# F405_V3_0_Red.net
KiCad netlist of a schematic drawn in Altium Designer
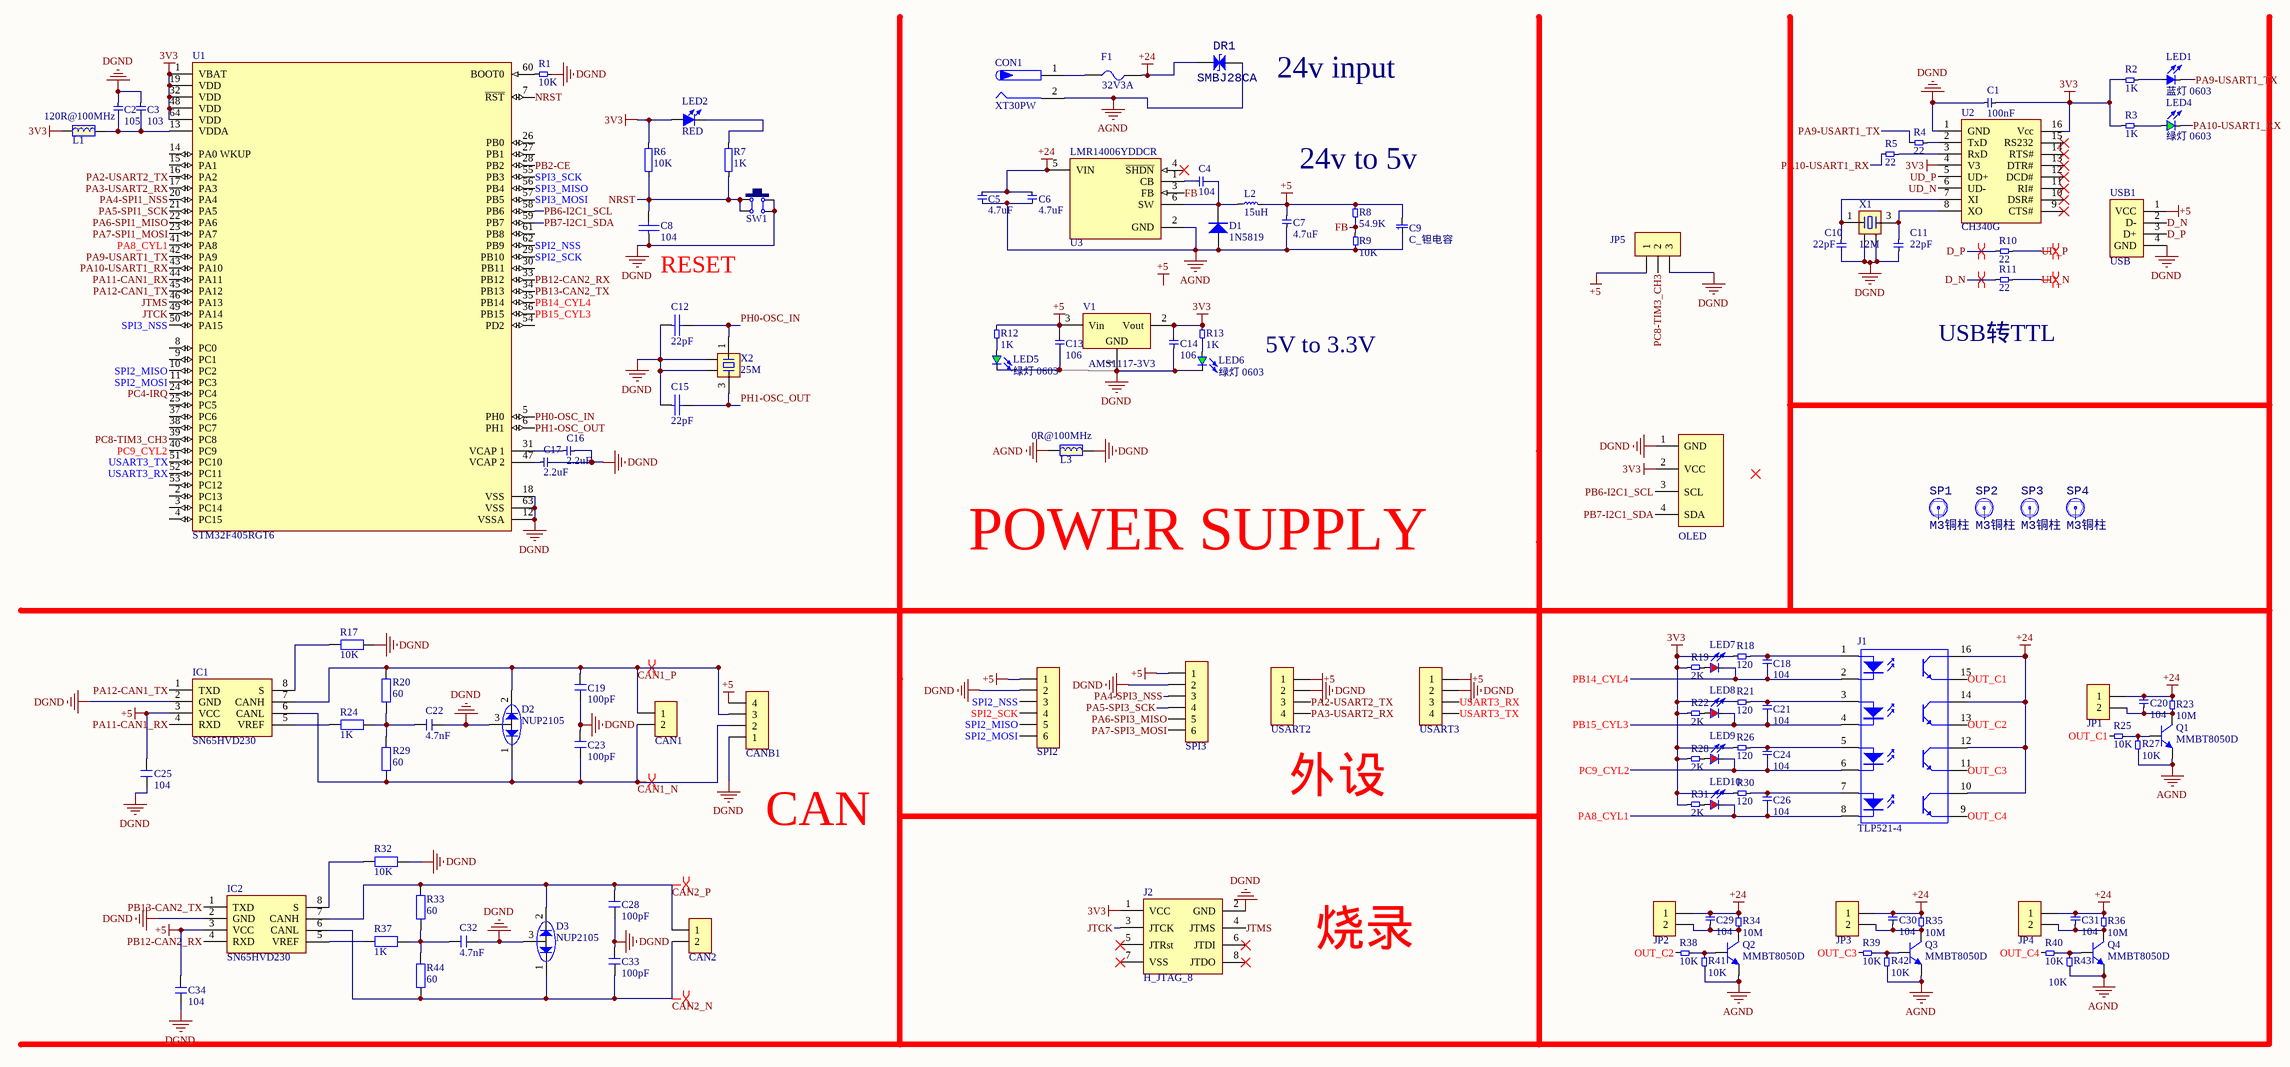
[diagram p0: F405_V3.0_Red.SchDoc]

(export (version "E")
  (design (tool "Eeschema 10.0.6"))
  (components
    (comp (ref "C1")
      (value "100nF")
      (footprint "C_0603")
      (description "无极性贴片电容")
      (libsource (lib "电阻电容电感库") (part "C_无极贴片"))
    )
    (comp (ref "C2")
      (value "105")
      (footprint "C_0603")
      (description "无极性贴片电容")
      (libsource (lib "电阻电容电感库") (part "C_无极贴片"))
    )
    (comp (ref "C3")
      (value "103")
      (footprint "C_0603")
      (description "无极性贴片电容")
      (libsource (lib "电阻电容电感库") (part "C_无极贴片"))
    )
    (comp (ref "C4")
      (value "104")
      (footprint "C_0603")
      (description "无极性贴片电容")
      (libsource (lib "电阻电容电感库") (part "C_无极贴片"))
    )
    (comp (ref "C5")
      (value "4.7uF")
      (footprint "C_0603")
      (description "无极性贴片电容")
      (libsource (lib "电阻电容电感库") (part "C_无极贴片"))
    )
    (comp (ref "C6")
      (value "4.7uF")
      (footprint "C_0603")
      (description "无极性贴片电容")
      (libsource (lib "电阻电容电感库") (part "C_无极贴片"))
    )
    (comp (ref "C7")
      (value "4.7uF")
      (footprint "C_0603")
      (description "无极性贴片电容")
      (libsource (lib "电阻电容电感库") (part "C_无极贴片"))
    )
    (comp (ref "C8")
      (value "104")
      (footprint "C 0603_L")
      (description "Capacitor")
      (libsource (lib "F446") (part "普通电容"))
    )
    (comp (ref "C9")
      (value "C_钽电容")
      (footprint "C_T-B_1210/3528-21")
      (description "有极性贴片钽电容")
      (libsource (lib "电阻电容电感库") (part "C_钽电容"))
    )
    (comp (ref "C10")
      (value "22pF")
      (footprint "C_0603")
      (description "无极性贴片电容")
      (libsource (lib "电阻电容电感库") (part "C_无极贴片"))
    )
    (comp (ref "C11")
      (value "22pF")
      (footprint "C_0603")
      (description "无极性贴片电容")
      (libsource (lib "电阻电容电感库") (part "C_无极贴片"))
    )
    (comp (ref "C12")
      (value "22pF")
      (footprint "C 0603_L")
      (description "Capacitor")
      (libsource (lib "F446") (part "普通电容"))
    )
    (comp (ref "C13")
      (value "106")
      (footprint "C_0603")
      (description "无极性贴片电容")
      (libsource (lib "电阻电容电感库") (part "C_无极贴片"))
    )
    (comp (ref "C14")
      (value "106")
      (footprint "C_0603")
      (description "无极性贴片电容")
      (libsource (lib "电阻电容电感库") (part "C_无极贴片"))
    )
    (comp (ref "C15")
      (value "22pF")
      (footprint "C 0603_L")
      (description "Capacitor")
      (libsource (lib "F446") (part "普通电容"))
    )
    (comp (ref "C16")
      (value "2.2uF")
      (footprint "C_0603")
      (description "无极性贴片电容")
      (libsource (lib "电阻电容电感库") (part "C_无极贴片"))
    )
    (comp (ref "C17")
      (value "2.2uF")
      (footprint "C_0603")
      (description "无极性贴片电容")
      (libsource (lib "电阻电容电感库") (part "C_无极贴片"))
    )
    (comp (ref "C18")
      (value "104")
      (footprint "C_0603")
      (description "无极性贴片电容")
      (libsource (lib "电阻电容电感库") (part "C_无极贴片"))
    )
    (comp (ref "C19")
      (value "100pF")
      (footprint "C 0603_L")
      (description "无极性贴片电容")
      (libsource (lib "3.1   - 电阻-电容-电感") (part "C"))
    )
    (comp (ref "C20")
      (value "104")
      (footprint "C_0603")
      (description "无极性贴片电容")
      (libsource (lib "电阻电容电感库") (part "C_无极贴片"))
    )
    (comp (ref "C21")
      (value "104")
      (footprint "C_0603")
      (description "无极性贴片电容")
      (libsource (lib "电阻电容电感库") (part "C_无极贴片"))
    )
    (comp (ref "C22")
      (value "4.7nF")
      (footprint "C 0603_L")
      (description "无极性贴片电容")
      (libsource (lib "3.1   - 电阻-电容-电感") (part "C"))
    )
    (comp (ref "C23")
      (value "100pF")
      (footprint "C 0603_L")
      (description "无极性贴片电容")
      (libsource (lib "3.1   - 电阻-电容-电感") (part "C"))
    )
    (comp (ref "C24")
      (value "104")
      (footprint "C_0603")
      (description "无极性贴片电容")
      (libsource (lib "电阻电容电感库") (part "C_无极贴片"))
    )
    (comp (ref "C25")
      (value "104")
      (footprint "C 0603_L")
      (description "无极性贴片电容")
      (libsource (lib "3.1   - 电阻-电容-电感") (part "C"))
    )
    (comp (ref "C26")
      (value "104")
      (footprint "C_0603")
      (description "无极性贴片电容")
      (libsource (lib "电阻电容电感库") (part "C_无极贴片"))
    )
    (comp (ref "C28")
      (value "100pF")
      (footprint "C 0603_L")
      (description "无极性贴片电容")
      (libsource (lib "3.1   - 电阻-电容-电感") (part "C"))
    )
    (comp (ref "C29")
      (value "104")
      (footprint "C_0603")
      (description "无极性贴片电容")
      (libsource (lib "电阻电容电感库") (part "C_无极贴片"))
    )
    (comp (ref "C30")
      (value "104")
      (footprint "C_0603")
      (description "无极性贴片电容")
      (libsource (lib "电阻电容电感库") (part "C_无极贴片"))
    )
    (comp (ref "C31")
      (value "104")
      (footprint "C_0603")
      (description "无极性贴片电容")
      (libsource (lib "电阻电容电感库") (part "C_无极贴片"))
    )
    (comp (ref "C32")
      (value "4.7nF")
      (footprint "C 0603_L")
      (description "无极性贴片电容")
      (libsource (lib "3.1   - 电阻-电容-电感") (part "C"))
    )
    (comp (ref "C33")
      (value "100pF")
      (footprint "C 0603_L")
      (description "无极性贴片电容")
      (libsource (lib "3.1   - 电阻-电容-电感") (part "C"))
    )
    (comp (ref "C34")
      (value "104")
      (footprint "C 0603_L")
      (description "无极性贴片电容")
      (libsource (lib "3.1   - 电阻-电容-电感") (part "C"))
    )
    (comp (ref "CAN1")
      (value "HDR-1X2")
      (footprint "XH2.54-LS-2P")
      (description "2P接插件")
      (libsource (lib "") (part "Header 2_1"))
    )
    (comp (ref "CAN2")
      (value "HDR-1X2")
      (footprint "XH2.54-LS-2P")
      (description "2P接插件")
      (libsource (lib "") (part "Header 2_1"))
    )
    (comp (ref "CANB1")
      (value "HDR-1X4")
      (footprint "XH2.54-LS-4P")
      (description "4P接插件")
      (libsource (lib "") (part "Header 4_1"))
    )
    (comp (ref "CON1")
      (value "XT30PW")
      (footprint "XT30PW-M")
      (description "XT30PW-M PCB板专用卧式连接器，低温升阻燃插头")
      (libsource (lib "AMASS") (part "XT30PW-M"))
    )
    (comp (ref "D1")
      (value "1N5819")
      (footprint "SOD-123")
      (description "肖特基二极管")
      (libsource (lib "8.1   - 二极管-整流桥") (part "1N5819"))
    )
    (comp (ref "D2")
      (value "NUP2105")
      (footprint "SOT23-3N")
      (description "表贴肖特基二极管")
      (libsource (lib "8.1   - 二极管-整流桥") (part "BAT54A"))
    )
    (comp (ref "D3")
      (value "NUP2105")
      (footprint "SOT23-3N")
      (description "表贴肖特基二极管")
      (libsource (lib "8.1   - 二极管-整流桥") (part "BAT54A"))
    )
    (comp (ref "DR1")
      (value "SMBJ28CA")
      (footprint "二极管-整流桥:SMB")
      (description "瞬态电压抑制二极管")
      (libsource (lib "8.1   - 二极管-整流桥") (part "DR"))
    )
    (comp (ref "F1")
      (value "32V3A")
      (footprint "FU 1206")
      (description "贴片保险丝")
      (libsource (lib "10.1 - 保险丝-晶振") (part "FU"))
    )
    (comp (ref "IC1")
      (value "SN65HVD230")
      (footprint "SOP8_M")
      (description "CAN芯片")
      (libsource (lib "F405底板") (part "SN65HVD1050"))
    )
    (comp (ref "IC2")
      (value "SN65HVD230")
      (footprint "SOP8_M")
      (description "CAN芯片")
      (libsource (lib "F405底板") (part "SN65HVD1050"))
    )
    (comp (ref "J1")
      (value "TLP521-4")
      (footprint "SOP16N_N")
      (description "4路开关光耦")
      (libsource (lib "11.1 - 传感元件") (part "TLP521-4"))
    )
    (comp (ref "J2")
      (value "H_JTAG_8")
      (footprint "IDC2.54-LI-2x4P")
      (description "调试器")
      (libsource (lib "F405") (part "H_JTAG_8"))
    )
    (comp (ref "JP1")
      (value "HDR-1X2")
      (footprint "XH2.54-LS-2P")
      (description "2P接插件")
      (libsource (lib "4.6   - 接插件-脚距2.54") (part "Header 2"))
    )
    (comp (ref "JP2")
      (value "HDR-1X2")
      (footprint "XH2.54-LS-2P")
      (description "2P接插件")
      (libsource (lib "4.6   - 接插件-脚距2.54") (part "Header 2"))
    )
    (comp (ref "JP3")
      (value "HDR-1X2")
      (footprint "XH2.54-LS-2P")
      (description "2P接插件")
      (libsource (lib "4.6   - 接插件-脚距2.54") (part "Header 2"))
    )
    (comp (ref "JP4")
      (value "HDR-1X2")
      (footprint "XH2.54-LS-2P")
      (description "2P接插件")
      (libsource (lib "4.6   - 接插件-脚距2.54") (part "Header 2"))
    )
    (comp (ref "JP5")
      (value "HDR-1X3")
      (footprint "XH2.54-LS-3P")
      (description "3P接插件")
      (libsource (lib "4.6   - 接插件-脚距2.54") (part "Header 3"))
    )
    (comp (ref "L1")
      (value "120R@100MHz")
      (footprint "L 0603_L")
      (description "磁珠")
      (libsource (lib "电阻电容电感库") (part "L_磁珠"))
    )
    (comp (ref "L2")
      (value "15uH")
      (footprint "CD43")
      (description "贴片屏蔽式功率电感")
      (libsource (lib "电阻电容电感库") (part "L_贴片功率"))
    )
    (comp (ref "L3")
      (value "0R@100MHz")
      (footprint "L 0603_L")
      (description "磁珠")
      (libsource (lib "电阻电容电感库") (part "L_磁珠"))
    )
    (comp (ref "LED1")
      (value "蓝灯 0603")
      (footprint "LED_SE")
      (description "发光二极管")
      (libsource (lib "LED") (part "0603 蓝灯"))
    )
    (comp (ref "LED2")
      (value "RED")
      (footprint "LED 0805R")
      (description "大功率LED")
      (libsource (lib "F446") (part "LED-SMD_1W"))
    )
    (comp (ref "LED4")
      (value "绿灯 0603")
      (footprint "LED_SE")
      (description "发光二极管")
      (libsource (lib "LED") (part "0603 绿灯"))
    )
    (comp (ref "LED5")
      (value "绿灯 0603")
      (footprint "LED_SE")
      (description "发光二极管")
      (libsource (lib "LED") (part "0603 绿灯"))
    )
    (comp (ref "LED6")
      (value "绿灯 0603")
      (footprint "LED_SE")
      (description "发光二极管")
      (libsource (lib "LED") (part "0603 绿灯"))
    )
    (comp (ref "LED7")
      (value "红灯 0603")
      (footprint "LED_SE")
      (description "发光二极管")
      (libsource (lib "LED") (part "0603 红灯"))
    )
    (comp (ref "LED8")
      (value "红灯 0603")
      (footprint "LED_SE")
      (description "发光二极管")
      (libsource (lib "LED") (part "0603 红灯"))
    )
    (comp (ref "LED9")
      (value "红灯 0603")
      (footprint "LED_SE")
      (description "发光二极管")
      (libsource (lib "LED") (part "0603 红灯"))
    )
    (comp (ref "LED10")
      (value "红灯 0603")
      (footprint "LED_SE")
      (description "发光二极管")
      (libsource (lib "LED") (part "0603 红灯"))
    )
    (comp (ref "OLED")
      (value "~")
      (footprint "OLED 4Pin 12864")
      (description "点阵屏")
      (libsource (lib "F446") (part "OLED"))
    )
    (comp (ref "Q1")
      (value "MMBT8050D")
      (footprint "SOT23-3N")
      (description "高压-NPN型")
      (libsource (lib "6.2   - 三极管") (part "MMBTA42"))
    )
    (comp (ref "Q2")
      (value "MMBT8050D")
      (footprint "SOT23-3N")
      (description "高压-NPN型")
      (libsource (lib "6.2   - 三极管") (part "MMBTA42"))
    )
    (comp (ref "Q3")
      (value "MMBT8050D")
      (footprint "SOT23-3N")
      (description "高压-NPN型")
      (libsource (lib "6.2   - 三极管") (part "MMBTA42"))
    )
    (comp (ref "Q4")
      (value "MMBT8050D")
      (footprint "SOT23-3N")
      (description "高压-NPN型")
      (libsource (lib "6.2   - 三极管") (part "MMBTA42"))
    )
    (comp (ref "R1")
      (value "10K")
      (footprint "R_0603")
      (description "贴片电阻")
      (libsource (lib "电阻电容电感库") (part "R_贴片"))
    )
    (comp (ref "R2")
      (value "1K")
      (footprint "R_0603")
      (description "贴片电阻")
      (libsource (lib "电阻电容电感库") (part "R_贴片"))
    )
    (comp (ref "R3")
      (value "1K")
      (footprint "R_0603")
      (description "贴片电阻")
      (libsource (lib "电阻电容电感库") (part "R_贴片"))
    )
    (comp (ref "R4")
      (value "22")
      (footprint "R_0603")
      (description "贴片电阻")
      (libsource (lib "电阻电容电感库") (part "R_贴片"))
    )
    (comp (ref "R5")
      (value "22")
      (footprint "R_0603")
      (description "贴片电阻")
      (libsource (lib "电阻电容电感库") (part "R_贴片"))
    )
    (comp (ref "R6") (value "10K") (footprint "R 0603_L") (libsource (lib "F446") (part "普通电阻")))
    (comp (ref "R7") (value "1K") (footprint "R 0603_L") (libsource (lib "F446") (part "普通电阻")))
    (comp (ref "R8")
      (value "54.9K")
      (footprint "R_0603")
      (description "贴片电阻")
      (libsource (lib "电阻电容电感库") (part "R_贴片"))
    )
    (comp (ref "R9")
      (value "10K")
      (footprint "R_0603")
      (description "贴片电阻")
      (libsource (lib "电阻电容电感库") (part "R_贴片"))
    )
    (comp (ref "R10")
      (value "22")
      (footprint "R_0603")
      (description "贴片电阻")
      (libsource (lib "电阻电容电感库") (part "R_贴片"))
    )
    (comp (ref "R11")
      (value "22")
      (footprint "R_0603")
      (description "贴片电阻")
      (libsource (lib "电阻电容电感库") (part "R_贴片"))
    )
    (comp (ref "R12")
      (value "1K")
      (footprint "R_0603")
      (description "贴片电阻")
      (libsource (lib "电阻电容电感库") (part "R_贴片"))
    )
    (comp (ref "R13")
      (value "1K")
      (footprint "R_0603")
      (description "贴片电阻")
      (libsource (lib "电阻电容电感库") (part "R_贴片"))
    )
    (comp (ref "R17")
      (value "10K")
      (footprint "R 0603_L")
      (description "贴片电阻")
      (libsource (lib "3.1   - 电阻-电容-电感") (part "R"))
    )
    (comp (ref "R18")
      (value "120")
      (footprint "R_0603")
      (description "贴片电阻")
      (libsource (lib "电阻电容电感库") (part "R_贴片"))
    )
    (comp (ref "R19")
      (value "2K")
      (footprint "R_0603")
      (description "贴片电阻")
      (libsource (lib "电阻电容电感库") (part "R_贴片"))
    )
    (comp (ref "R20")
      (value "60")
      (footprint "R 0603_L")
      (description "贴片电阻")
      (libsource (lib "3.1   - 电阻-电容-电感") (part "R"))
    )
    (comp (ref "R21")
      (value "120")
      (footprint "R_0603")
      (description "贴片电阻")
      (libsource (lib "电阻电容电感库") (part "R_贴片"))
    )
    (comp (ref "R22")
      (value "2K")
      (footprint "R_0603")
      (description "贴片电阻")
      (libsource (lib "电阻电容电感库") (part "R_贴片"))
    )
    (comp (ref "R23")
      (value "10M")
      (footprint "R_0805")
      (description "贴片电阻")
      (libsource (lib "电阻电容电感库") (part "R_贴片"))
    )
    (comp (ref "R24")
      (value "1K")
      (footprint "R 0603_L")
      (description "贴片电阻")
      (libsource (lib "3.1   - 电阻-电容-电感") (part "R"))
    )
    (comp (ref "R25")
      (value "10K")
      (footprint "R_0603")
      (description "贴片电阻")
      (libsource (lib "电阻电容电感库") (part "R_贴片"))
    )
    (comp (ref "R26")
      (value "120")
      (footprint "R_0603")
      (description "贴片电阻")
      (libsource (lib "电阻电容电感库") (part "R_贴片"))
    )
    (comp (ref "R27")
      (value "10K")
      (footprint "R_0603")
      (description "贴片电阻")
      (libsource (lib "电阻电容电感库") (part "R_贴片"))
    )
    (comp (ref "R28")
      (value "2K")
      (footprint "R_0603")
      (description "贴片电阻")
      (libsource (lib "电阻电容电感库") (part "R_贴片"))
    )
    (comp (ref "R29")
      (value "60")
      (footprint "R 0603_L")
      (description "贴片电阻")
      (libsource (lib "3.1   - 电阻-电容-电感") (part "R"))
    )
    (comp (ref "R30")
      (value "120")
      (footprint "R_0603")
      (description "贴片电阻")
      (libsource (lib "电阻电容电感库") (part "R_贴片"))
    )
    (comp (ref "R31")
      (value "2K")
      (footprint "R_0603")
      (description "贴片电阻")
      (libsource (lib "电阻电容电感库") (part "R_贴片"))
    )
    (comp (ref "R32")
      (value "10K")
      (footprint "R 0603_L")
      (description "贴片电阻")
      (libsource (lib "3.1   - 电阻-电容-电感") (part "R"))
    )
    (comp (ref "R33")
      (value "60")
      (footprint "R 0603_L")
      (description "贴片电阻")
      (libsource (lib "3.1   - 电阻-电容-电感") (part "R"))
    )
    (comp (ref "R34")
      (value "10M")
      (footprint "R_0805")
      (description "贴片电阻")
      (libsource (lib "电阻电容电感库") (part "R_贴片"))
    )
    (comp (ref "R35")
      (value "10M")
      (footprint "R_0805")
      (description "贴片电阻")
      (libsource (lib "电阻电容电感库") (part "R_贴片"))
    )
    (comp (ref "R36")
      (value "10M")
      (footprint "R_0805")
      (description "贴片电阻")
      (libsource (lib "电阻电容电感库") (part "R_贴片"))
    )
    (comp (ref "R37")
      (value "1K")
      (footprint "R 0603_L")
      (description "贴片电阻")
      (libsource (lib "3.1   - 电阻-电容-电感") (part "R"))
    )
    (comp (ref "R38")
      (value "10K")
      (footprint "R_0603")
      (description "贴片电阻")
      (libsource (lib "电阻电容电感库") (part "R_贴片"))
    )
    (comp (ref "R39")
      (value "10K")
      (footprint "R_0603")
      (description "贴片电阻")
      (libsource (lib "电阻电容电感库") (part "R_贴片"))
    )
    (comp (ref "R40")
      (value "10K")
      (footprint "R_0603")
      (description "贴片电阻")
      (libsource (lib "电阻电容电感库") (part "R_贴片"))
    )
    (comp (ref "R41")
      (value "10K")
      (footprint "R_0603")
      (description "贴片电阻")
      (libsource (lib "电阻电容电感库") (part "R_贴片"))
    )
    (comp (ref "R42")
      (value "10K")
      (footprint "R_0603")
      (description "贴片电阻")
      (libsource (lib "电阻电容电感库") (part "R_贴片"))
    )
    (comp (ref "R43")
      (value "10K")
      (footprint "R_0603")
      (description "贴片电阻")
      (libsource (lib "电阻电容电感库") (part "R_贴片"))
    )
    (comp (ref "R44")
      (value "60")
      (footprint "R 0603_L")
      (description "贴片电阻")
      (libsource (lib "3.1   - 电阻-电容-电感") (part "R"))
    )
    (comp (ref "SP1")
      (value "M3铜柱")
      (footprint "M3x4_L")
      (description "铜柱")
      (libsource (lib "15.1 - 未分类器件") (part "铜柱小焊盘"))
    )
    (comp (ref "SP2")
      (value "M3铜柱")
      (footprint "M3x4_L")
      (description "铜柱")
      (libsource (lib "15.1 - 未分类器件") (part "铜柱小焊盘"))
    )
    (comp (ref "SP3")
      (value "M3铜柱")
      (footprint "M3x4_L")
      (description "铜柱")
      (libsource (lib "15.1 - 未分类器件") (part "铜柱小焊盘"))
    )
    (comp (ref "SP4")
      (value "M3铜柱")
      (footprint "M3x4_L")
      (description "铜柱")
      (libsource (lib "15.1 - 未分类器件") (part "铜柱小焊盘"))
    )
    (comp (ref "SPI2")
      (value "HDR-1X6")
      (footprint "XH2.54-LS-6P")
      (description "6P接插件")
      (libsource (lib "钝角") (part "Header 6"))
    )
    (comp (ref "SPI3")
      (value "HDR-1X6")
      (footprint "XH2.54-LS-6P")
      (description "6P接插件")
      (libsource (lib "钝角") (part "Header 6"))
    )
    (comp (ref "SW1")
      (value "6x6x5")
      (footprint "TSW SMD-6*6*8")
      (description "贴片6x6轻触开关")
      (libsource (lib "5.1   - 按键-开关") (part "TSW SMD-6x6"))
    )
    (comp (ref "U1")
      (value "STM32F405RGT6")
      (footprint "LQFP64 10x10_N")
      (libsource (lib "2.1   - STM32系列单片机") (part "STM32F405RGT6"))
    )
    (comp (ref "U2")
      (value "CH340G")
      (footprint "SOP16_N")
      (description "串口转USB")
      (libsource (lib "1.1   - IC芯片") (part "CH340G"))
    )
    (comp (ref "U3")
      (value "LMR14006YDDCR")
      (footprint "SOT23-6L")
      (description "SIMPLE SWITCHER® 4-V to 40-V, 600-mA step-down converter with Low Iq 6-SOT-23-THIN -40 to 125")
      (libsource (lib "高级IC") (part "LMR14006YDDCR"))
    )
    (comp (ref "USART2")
      (value "HDR-1X4")
      (footprint "XH2.54-LS-4P")
      (description "4P接插件")
      (libsource (lib "4.6   - 接插件-脚距2.54") (part "Header 4"))
    )
    (comp (ref "USART3")
      (value "HDR-1X4")
      (footprint "XH2.54-LS-4P")
      (description "4P接插件")
      (libsource (lib "4.6   - 接插件-脚距2.54") (part "Header 4"))
    )
    (comp (ref "USB1")
      (value "USB")
      (footprint "USB-A/S_A")
      (description "USB-A型母接口")
      (libsource (lib "4.1   - 接口类") (part "USB-A/S"))
    )
    (comp (ref "V1")
      (value "AMS1117-3V3")
      (footprint "SOT223_N")
      (description "三端稳压芯片")
      (libsource (lib "1.3   - 电源类芯片") (part "AMS1117"))
    )
    (comp (ref "X1")
      (value "12M")
      (footprint "OSC 3225-4P")
      (description "4脚无源晶振")
      (libsource (lib "10.1 - 保险丝-晶振") (part "XTAL-4P"))
    )
    (comp (ref "X2")
      (value "25M")
      (footprint "OSC 3225-4P")
      (description "4脚无源晶振")
      (libsource (lib "F446") (part "XTAL-4P"))
    )
  )
  (nets
    (net (code "1") (name "+5") (class "Default")
      (node (ref "C13") (pin "2") (pinfunction "2_2") (pintype "passive"))
      (node (ref "C25") (pin "2") (pinfunction "2_2") (pintype "passive"))
      (node (ref "C34") (pin "2") (pinfunction "2_2") (pintype "passive"))
      (node (ref "C7") (pin "1") (pinfunction "1_1") (pintype "passive"))
      (node (ref "C9") (pin "2") (pinfunction "2_2") (pintype "passive"))
      (node (ref "CANB1") (pin "4") (pinfunction "4_4") (pintype "passive"))
      (node (ref "IC1") (pin "3") (pinfunction "VCC_3") (pintype "passive"))
      (node (ref "IC2") (pin "3") (pinfunction "VCC_3") (pintype "passive"))
      (node (ref "JP5") (pin "1") (pinfunction "1_1") (pintype "passive"))
      (node (ref "L2") (pin "2") (pinfunction "2_2") (pintype "passive"))
      (node (ref "R12") (pin "2") (pintype "passive"))
      (node (ref "R8") (pin "2") (pintype "passive"))
      (node (ref "SPI2") (pin "1") (pinfunction "1_1") (pintype "passive"))
      (node (ref "SPI3") (pin "1") (pinfunction "1_1") (pintype "passive"))
      (node (ref "USART2") (pin "1") (pinfunction "1_1") (pintype "passive"))
      (node (ref "USART3") (pin "1") (pinfunction "1_1") (pintype "passive"))
      (node (ref "USB1") (pin "1") (pinfunction "VCC_1") (pintype "passive"))
      (node (ref "V1") (pin "3") (pinfunction "Vin_3") (pintype "passive"))
    )
    (net (code "2") (name "+24") (class "Default")
      (node (ref "C20") (pin "2") (pinfunction "2_2") (pintype "passive"))
      (node (ref "C29") (pin "2") (pinfunction "2_2") (pintype "passive"))
      (node (ref "C30") (pin "2") (pinfunction "2_2") (pintype "passive"))
      (node (ref "C31") (pin "2") (pinfunction "2_2") (pintype "passive"))
      (node (ref "C5") (pin "2") (pinfunction "2_2") (pintype "passive"))
      (node (ref "C6") (pin "2") (pinfunction "2_2") (pintype "passive"))
      (node (ref "DR1") (pin "2") (pinfunction "K_2") (pintype "passive"))
      (node (ref "F1") (pin "2") (pinfunction "2_2") (pintype "passive"))
      (node (ref "J1") (pin "10") (pinfunction "4C_10") (pintype "passive"))
      (node (ref "J1") (pin "12") (pinfunction "3C_12") (pintype "passive"))
      (node (ref "J1") (pin "14") (pinfunction "2C_14") (pintype "passive"))
      (node (ref "J1") (pin "16") (pinfunction "1C_16") (pintype "passive"))
      (node (ref "JP1") (pin "1") (pinfunction "1_1") (pintype "passive"))
      (node (ref "JP2") (pin "1") (pinfunction "1_1") (pintype "passive"))
      (node (ref "JP3") (pin "1") (pinfunction "1_1") (pintype "passive"))
      (node (ref "JP4") (pin "1") (pinfunction "1_1") (pintype "passive"))
      (node (ref "R23") (pin "2") (pintype "passive"))
      (node (ref "R34") (pin "2") (pintype "passive"))
      (node (ref "R35") (pin "2") (pintype "passive"))
      (node (ref "R36") (pin "2") (pintype "passive"))
      (node (ref "U3") (pin "5") (pinfunction "VIN_5") (pintype "power_in"))
    )
    (net (code "3") (name "/CAN1_N") (class "Default")
      (node (ref "C23") (pin "2") (pinfunction "2_2") (pintype "passive"))
      (node (ref "CAN1") (pin "2") (pinfunction "2_2") (pintype "passive"))
      (node (ref "CANB1") (pin "2") (pinfunction "2_2") (pintype "passive"))
      (node (ref "D2") (pin "1") (pinfunction "1_1") (pintype "passive"))
      (node (ref "IC1") (pin "6") (pinfunction "CANL_6") (pintype "passive"))
      (node (ref "R29") (pin "2") (pinfunction "2_2") (pintype "passive"))
    )
    (net (code "4") (name "/CAN1_P") (class "Default")
      (node (ref "C19") (pin "1") (pinfunction "1_1") (pintype "passive"))
      (node (ref "CAN1") (pin "1") (pinfunction "1_1") (pintype "passive"))
      (node (ref "CANB1") (pin "3") (pinfunction "3_3") (pintype "passive"))
      (node (ref "D2") (pin "2") (pinfunction "2_2") (pintype "passive"))
      (node (ref "IC1") (pin "7") (pinfunction "CANH_7") (pintype "passive"))
      (node (ref "R20") (pin "2") (pinfunction "2_2") (pintype "passive"))
    )
    (net (code "5") (name "/CAN2_N") (class "Default")
      (node (ref "C33") (pin "2") (pinfunction "2_2") (pintype "passive"))
      (node (ref "CAN2") (pin "2") (pinfunction "2_2") (pintype "passive"))
      (node (ref "D3") (pin "1") (pinfunction "1_1") (pintype "passive"))
      (node (ref "IC2") (pin "6") (pinfunction "CANL_6") (pintype "passive"))
      (node (ref "R44") (pin "2") (pinfunction "2_2") (pintype "passive"))
    )
    (net (code "6") (name "/CAN2_P") (class "Default")
      (node (ref "C28") (pin "1") (pinfunction "1_1") (pintype "passive"))
      (node (ref "CAN2") (pin "1") (pinfunction "1_1") (pintype "passive"))
      (node (ref "D3") (pin "2") (pinfunction "2_2") (pintype "passive"))
      (node (ref "IC2") (pin "7") (pinfunction "CANH_7") (pintype "passive"))
      (node (ref "R33") (pin "2") (pinfunction "2_2") (pintype "passive"))
    )
    (net (code "7") (name "/D_N") (class "Default")
      (node (ref "R11") (pin "1") (pintype "passive"))
      (node (ref "USB1") (pin "2") (pinfunction "D-_2") (pintype "passive"))
    )
    (net (code "8") (name "/D_P") (class "Default")
      (node (ref "R10") (pin "1") (pintype "passive"))
      (node (ref "USB1") (pin "3") (pinfunction "D+_3") (pintype "passive"))
    )
    (net (code "9") (name "/FB") (class "Default")
      (node (ref "R8") (pin "1") (pintype "passive"))
      (node (ref "R9") (pin "1") (pintype "passive"))
      (node (ref "U3") (pin "3") (pinfunction "FB_3") (pintype "input"))
    )
    (net (code "10") (name "/JTCK") (class "Default")
      (node (ref "J2") (pin "3") (pinfunction "JTCK_3") (pintype "passive"))
      (node (ref "U1") (pin "49") (pinfunction "PA14_49") (pintype "bidirectional"))
    )
    (net (code "11") (name "/JTMS") (class "Default")
      (node (ref "J2") (pin "4") (pinfunction "JTMS_4") (pintype "passive"))
      (node (ref "U1") (pin "46") (pinfunction "PA13_46") (pintype "bidirectional"))
    )
    (net (code "12") (name "/NRST") (class "Default")
      (node (ref "C8") (pin "2") (pinfunction "2_2") (pintype "passive"))
      (node (ref "R6") (pin "1") (pinfunction "1_1") (pintype "passive"))
      (node (ref "R7") (pin "1") (pinfunction "1_1") (pintype "passive"))
      (node (ref "SW1") (pin "1") (pinfunction "1_1") (pintype "passive"))
      (node (ref "SW1") (pin "4") (pinfunction "4_4") (pintype "passive"))
      (node (ref "U1") (pin "7") (pinfunction "~{RST}_7") (pintype "bidirectional"))
    )
    (net (code "13") (name "/OUT_C1") (class "Default")
      (node (ref "J1") (pin "15") (pinfunction "1E_15") (pintype "passive"))
      (node (ref "R25") (pin "1") (pintype "passive"))
    )
    (net (code "14") (name "/OUT_C2") (class "Default")
      (node (ref "J1") (pin "13") (pinfunction "2E_13") (pintype "passive"))
      (node (ref "R38") (pin "1") (pintype "passive"))
    )
    (net (code "15") (name "/OUT_C3") (class "Default")
      (node (ref "J1") (pin "11") (pinfunction "3E_11") (pintype "passive"))
      (node (ref "R39") (pin "1") (pintype "passive"))
    )
    (net (code "16") (name "/OUT_C4") (class "Default")
      (node (ref "J1") (pin "9") (pinfunction "4E_9") (pintype "passive"))
      (node (ref "R40") (pin "1") (pintype "passive"))
    )
    (net (code "17") (name "/PA2-USART2_TX") (class "Default")
      (node (ref "U1") (pin "16") (pinfunction "PA2_16") (pintype "bidirectional"))
      (node (ref "USART2") (pin "3") (pinfunction "3_3") (pintype "passive"))
    )
    (net (code "18") (name "/PA3-USART2_RX") (class "Default")
      (node (ref "U1") (pin "17") (pinfunction "PA3_17") (pintype "bidirectional"))
      (node (ref "USART2") (pin "4") (pinfunction "4_4") (pintype "passive"))
    )
    (net (code "19") (name "/PA4-SPI1_NSS") (class "Default")
      (node (ref "U1") (pin "20") (pinfunction "PA4_20") (pintype "bidirectional"))
    )
    (net (code "20") (name "/PA4-SPI3_NSS") (class "Default")
      (node (ref "SPI3") (pin "3") (pinfunction "3_3") (pintype "passive"))
    )
    (net (code "21") (name "/PA5-SPI1_SCK") (class "Default")
      (node (ref "U1") (pin "21") (pinfunction "PA5_21") (pintype "bidirectional"))
    )
    (net (code "22") (name "/PA5-SPI3_SCK") (class "Default")
      (node (ref "SPI3") (pin "4") (pinfunction "4_4") (pintype "passive"))
    )
    (net (code "23") (name "/PA6-SPI1_MISO") (class "Default")
      (node (ref "U1") (pin "22") (pinfunction "PA6_22") (pintype "bidirectional"))
    )
    (net (code "24") (name "/PA6-SPI3_MISO") (class "Default")
      (node (ref "SPI3") (pin "5") (pinfunction "5_5") (pintype "passive"))
    )
    (net (code "25") (name "/PA7-SPI1_MOSI") (class "Default")
      (node (ref "U1") (pin "23") (pinfunction "PA7_23") (pintype "bidirectional"))
    )
    (net (code "26") (name "/PA7-SPI3_MOSI") (class "Default")
      (node (ref "SPI3") (pin "6") (pinfunction "6_6") (pintype "passive"))
    )
    (net (code "27") (name "/PA8_CYL1") (class "Default")
      (node (ref "C26") (pin "1") (pinfunction "1_1") (pintype "passive"))
      (node (ref "J1") (pin "8") (pinfunction "4K_8") (pintype "passive"))
      (node (ref "LED10") (pin "K") (pinfunction "K_K") (pintype "passive"))
      (node (ref "U1") (pin "41") (pinfunction "PA8_41") (pintype "bidirectional"))
    )
    (net (code "28") (name "/PA9-USART1_TX") (class "Default")
      (node (ref "LED1") (pin "K") (pinfunction "K_K") (pintype "passive"))
      (node (ref "R4") (pin "1") (pintype "passive"))
      (node (ref "U1") (pin "42") (pinfunction "PA9_42") (pintype "bidirectional"))
    )
    (net (code "29") (name "/PA10-USART1_RX") (class "Default")
      (node (ref "LED4") (pin "K") (pinfunction "K_K") (pintype "passive"))
      (node (ref "R5") (pin "1") (pintype "passive"))
      (node (ref "U1") (pin "43") (pinfunction "PA10_43") (pintype "bidirectional"))
    )
    (net (code "30") (name "/PA11-CAN1_RX") (class "Default")
      (node (ref "IC1") (pin "4") (pinfunction "RXD_4") (pintype "passive"))
      (node (ref "U1") (pin "44") (pinfunction "PA11_44") (pintype "bidirectional"))
    )
    (net (code "31") (name "/PA12-CAN1_TX") (class "Default")
      (node (ref "IC1") (pin "1") (pinfunction "TXD_1") (pintype "passive"))
      (node (ref "U1") (pin "45") (pinfunction "PA12_45") (pintype "bidirectional"))
    )
    (net (code "32") (name "/PB2-CE") (class "Default")
      (node (ref "U1") (pin "28") (pinfunction "PB2_28") (pintype "bidirectional"))
    )
    (net (code "33") (name "/PB6-I2C1_SCL") (class "Default")
      (node (ref "OLED") (pin "3") (pinfunction "SCL_3") (pintype "passive"))
      (node (ref "U1") (pin "58") (pinfunction "PB6_58") (pintype "bidirectional"))
    )
    (net (code "34") (name "/PB7-I2C1_SDA") (class "Default")
      (node (ref "OLED") (pin "4") (pinfunction "SDA_4") (pintype "passive"))
      (node (ref "U1") (pin "59") (pinfunction "PB7_59") (pintype "bidirectional"))
    )
    (net (code "35") (name "/PB12-CAN2_RX") (class "Default")
      (node (ref "IC2") (pin "4") (pinfunction "RXD_4") (pintype "passive"))
      (node (ref "U1") (pin "33") (pinfunction "PB12_33") (pintype "bidirectional"))
    )
    (net (code "36") (name "/PB13-CAN2_TX") (class "Default")
      (node (ref "IC2") (pin "1") (pinfunction "TXD_1") (pintype "passive"))
      (node (ref "U1") (pin "34") (pinfunction "PB13_34") (pintype "bidirectional"))
    )
    (net (code "37") (name "/PB14_CYL4") (class "Default")
      (node (ref "C18") (pin "1") (pinfunction "1_1") (pintype "passive"))
      (node (ref "J1") (pin "2") (pinfunction "1K_2") (pintype "passive"))
      (node (ref "LED7") (pin "K") (pinfunction "K_K") (pintype "passive"))
      (node (ref "U1") (pin "35") (pinfunction "PB14_35") (pintype "bidirectional"))
    )
    (net (code "38") (name "/PB15_CYL3") (class "Default")
      (node (ref "C21") (pin "1") (pinfunction "1_1") (pintype "passive"))
      (node (ref "J1") (pin "4") (pinfunction "2K_4") (pintype "passive"))
      (node (ref "LED8") (pin "K") (pinfunction "K_K") (pintype "passive"))
      (node (ref "U1") (pin "36") (pinfunction "PB15_36") (pintype "bidirectional"))
    )
    (net (code "39") (name "/PC4-IRQ") (class "Default")
      (node (ref "U1") (pin "24") (pinfunction "PC4_24") (pintype "bidirectional"))
    )
    (net (code "40") (name "/PC8-TIM3_CH3") (class "Default")
      (node (ref "JP5") (pin "2") (pinfunction "2_2") (pintype "passive"))
      (node (ref "U1") (pin "39") (pinfunction "PC8_39") (pintype "bidirectional"))
    )
    (net (code "41") (name "/PC9_CYL2") (class "Default")
      (node (ref "C24") (pin "1") (pinfunction "1_1") (pintype "passive"))
      (node (ref "J1") (pin "6") (pinfunction "3K_6") (pintype "passive"))
      (node (ref "LED9") (pin "K") (pinfunction "K_K") (pintype "passive"))
      (node (ref "U1") (pin "40") (pinfunction "PC9_40") (pintype "bidirectional"))
    )
    (net (code "42") (name "/PH0-OSC_IN") (class "Default")
      (node (ref "C12") (pin "2") (pinfunction "2_2") (pintype "passive"))
      (node (ref "U1") (pin "5") (pinfunction "PH0_5") (pintype "bidirectional"))
      (node (ref "X2") (pin "1") (pinfunction "1_1") (pintype "passive"))
    )
    (net (code "43") (name "/PH1-OSC_OUT") (class "Default")
      (node (ref "C15") (pin "2") (pinfunction "2_2") (pintype "passive"))
      (node (ref "U1") (pin "6") (pinfunction "PH1_6") (pintype "bidirectional"))
      (node (ref "X2") (pin "3") (pinfunction "3_3") (pintype "passive"))
    )
    (net (code "44") (name "/SPI2_MISO") (class "Default")
      (node (ref "SPI2") (pin "5") (pinfunction "5_5") (pintype "passive"))
      (node (ref "U1") (pin "10") (pinfunction "PC2_10") (pintype "bidirectional"))
    )
    (net (code "45") (name "/SPI2_MOSI") (class "Default")
      (node (ref "SPI2") (pin "6") (pinfunction "6_6") (pintype "passive"))
      (node (ref "U1") (pin "11") (pinfunction "PC3_11") (pintype "bidirectional"))
    )
    (net (code "46") (name "/SPI2_NSS") (class "Default")
      (node (ref "SPI2") (pin "3") (pinfunction "3_3") (pintype "passive"))
      (node (ref "U1") (pin "62") (pinfunction "PB9_62") (pintype "bidirectional"))
    )
    (net (code "47") (name "/SPI2_SCK") (class "Default")
      (node (ref "SPI2") (pin "4") (pinfunction "4_4") (pintype "passive"))
      (node (ref "U1") (pin "29") (pinfunction "PB10_29") (pintype "bidirectional"))
    )
    (net (code "48") (name "/SPI3_MISO") (class "Default")
      (node (ref "U1") (pin "56") (pinfunction "PB4_56") (pintype "bidirectional"))
    )
    (net (code "49") (name "/SPI3_MOSI") (class "Default")
      (node (ref "U1") (pin "57") (pinfunction "PB5_57") (pintype "bidirectional"))
    )
    (net (code "50") (name "/SPI3_NSS") (class "Default")
      (node (ref "U1") (pin "50") (pinfunction "PA15_50") (pintype "bidirectional"))
    )
    (net (code "51") (name "/SPI3_SCK") (class "Default")
      (node (ref "U1") (pin "55") (pinfunction "PB3_55") (pintype "bidirectional"))
    )
    (net (code "52") (name "/UD_N") (class "Default")
      (node (ref "R11") (pin "2") (pintype "passive"))
      (node (ref "U2") (pin "6") (pinfunction "UD-_6") (pintype "passive"))
    )
    (net (code "53") (name "/UD_P") (class "Default")
      (node (ref "R10") (pin "2") (pintype "passive"))
      (node (ref "U2") (pin "5") (pinfunction "UD+_5") (pintype "passive"))
    )
    (net (code "54") (name "/USART3_RX") (class "Default")
      (node (ref "U1") (pin "52") (pinfunction "PC11_52") (pintype "bidirectional"))
      (node (ref "USART3") (pin "3") (pinfunction "3_3") (pintype "passive"))
    )
    (net (code "55") (name "/USART3_TX") (class "Default")
      (node (ref "U1") (pin "51") (pinfunction "PC10_51") (pintype "bidirectional"))
      (node (ref "USART3") (pin "4") (pinfunction "4_4") (pintype "passive"))
    )
    (net (code "56") (name "3V3") (class "Default")
      (node (ref "C1") (pin "2") (pinfunction "2_2") (pintype "passive"))
      (node (ref "C14") (pin "2") (pinfunction "2_2") (pintype "passive"))
      (node (ref "J2") (pin "1") (pinfunction "VCC_1") (pintype "passive"))
      (node (ref "L1") (pin "1") (pintype "passive"))
      (node (ref "LED2") (pin "1") (pinfunction "A_1") (pintype "passive"))
      (node (ref "OLED") (pin "2") (pinfunction "VCC_2") (pintype "passive"))
      (node (ref "R13") (pin "2") (pintype "passive"))
      (node (ref "R18") (pin "1") (pintype "passive"))
      (node (ref "R19") (pin "2") (pintype "passive"))
      (node (ref "R2") (pin "1") (pintype "passive"))
      (node (ref "R21") (pin "1") (pintype "passive"))
      (node (ref "R22") (pin "2") (pintype "passive"))
      (node (ref "R26") (pin "1") (pintype "passive"))
      (node (ref "R28") (pin "2") (pintype "passive"))
      (node (ref "R3") (pin "1") (pintype "passive"))
      (node (ref "R30") (pin "1") (pintype "passive"))
      (node (ref "R31") (pin "2") (pintype "passive"))
      (node (ref "R6") (pin "2") (pinfunction "2_2") (pintype "passive"))
      (node (ref "U1") (pin "1") (pinfunction "VBAT_1") (pintype "power_in"))
      (node (ref "U1") (pin "19") (pinfunction "VDD_19") (pintype "power_in"))
      (node (ref "U1") (pin "32") (pinfunction "VDD_32") (pintype "power_in"))
      (node (ref "U1") (pin "48") (pinfunction "VDD_48") (pintype "power_in"))
      (node (ref "U1") (pin "64") (pinfunction "VDD_64") (pintype "power_in"))
      (node (ref "U2") (pin "16") (pinfunction "Vcc_16") (pintype "passive"))
      (node (ref "U2") (pin "4") (pinfunction "V3_4") (pintype "passive"))
      (node (ref "V1") (pin "2") (pinfunction "Vout_2") (pintype "passive"))
    )
    (net (code "57") (name "AGND") (class "Default")
      (node (ref "C5") (pin "1") (pinfunction "1_1") (pintype "passive"))
      (node (ref "C6") (pin "1") (pinfunction "1_1") (pintype "passive"))
      (node (ref "C7") (pin "2") (pinfunction "2_2") (pintype "passive"))
      (node (ref "C9") (pin "1") (pinfunction "1_1") (pintype "passive"))
      (node (ref "CON1") (pin "2") (pintype "power_in"))
      (node (ref "D1") (pin "1") (pinfunction "A_1") (pintype "passive"))
      (node (ref "DR1") (pin "1") (pinfunction "A_1") (pintype "passive"))
      (node (ref "L3") (pin "1") (pintype "passive"))
      (node (ref "Q1") (pin "2") (pinfunction "E_2") (pintype "passive"))
      (node (ref "Q2") (pin "2") (pinfunction "E_2") (pintype "passive"))
      (node (ref "Q3") (pin "2") (pinfunction "E_2") (pintype "passive"))
      (node (ref "Q4") (pin "2") (pinfunction "E_2") (pintype "passive"))
      (node (ref "R27") (pin "1") (pintype "passive"))
      (node (ref "R41") (pin "1") (pintype "passive"))
      (node (ref "R42") (pin "1") (pintype "passive"))
      (node (ref "R43") (pin "1") (pintype "passive"))
      (node (ref "R9") (pin "2") (pintype "passive"))
      (node (ref "U3") (pin "2") (pinfunction "GND_2") (pintype "power_in"))
    )
    (net (code "58") (name "DGND") (class "Default")
      (node (ref "C1") (pin "1") (pinfunction "1_1") (pintype "passive"))
      (node (ref "C10") (pin "1") (pinfunction "1_1") (pintype "passive"))
      (node (ref "C11") (pin "1") (pinfunction "1_1") (pintype "passive"))
      (node (ref "C12") (pin "1") (pinfunction "1_1") (pintype "passive"))
      (node (ref "C13") (pin "1") (pinfunction "1_1") (pintype "passive"))
      (node (ref "C14") (pin "1") (pinfunction "1_1") (pintype "passive"))
      (node (ref "C15") (pin "1") (pinfunction "1_1") (pintype "passive"))
      (node (ref "C16") (pin "2") (pinfunction "2_2") (pintype "passive"))
      (node (ref "C17") (pin "2") (pinfunction "2_2") (pintype "passive"))
      (node (ref "C19") (pin "2") (pinfunction "2_2") (pintype "passive"))
      (node (ref "C2") (pin "2") (pinfunction "2_2") (pintype "passive"))
      (node (ref "C22") (pin "2") (pinfunction "2_2") (pintype "passive"))
      (node (ref "C23") (pin "1") (pinfunction "1_1") (pintype "passive"))
      (node (ref "C25") (pin "1") (pinfunction "1_1") (pintype "passive"))
      (node (ref "C28") (pin "2") (pinfunction "2_2") (pintype "passive"))
      (node (ref "C3") (pin "2") (pinfunction "2_2") (pintype "passive"))
      (node (ref "C32") (pin "2") (pinfunction "2_2") (pintype "passive"))
      (node (ref "C33") (pin "1") (pinfunction "1_1") (pintype "passive"))
      (node (ref "C34") (pin "1") (pinfunction "1_1") (pintype "passive"))
      (node (ref "C8") (pin "1") (pinfunction "1_1") (pintype "passive"))
      (node (ref "CANB1") (pin "1") (pinfunction "1_1") (pintype "passive"))
      (node (ref "D2") (pin "3") (pinfunction "3_3") (pintype "passive"))
      (node (ref "D3") (pin "3") (pinfunction "3_3") (pintype "passive"))
      (node (ref "IC1") (pin "2") (pinfunction "GND_2") (pintype "passive"))
      (node (ref "IC2") (pin "2") (pinfunction "GND_2") (pintype "passive"))
      (node (ref "J2") (pin "2") (pinfunction "GND_2") (pintype "passive"))
      (node (ref "JP5") (pin "3") (pinfunction "3_3") (pintype "passive"))
      (node (ref "L3") (pin "2") (pinfunction "2_2") (pintype "passive"))
      (node (ref "LED5") (pin "K") (pinfunction "K_K") (pintype "passive"))
      (node (ref "LED6") (pin "K") (pinfunction "K_K") (pintype "passive"))
      (node (ref "OLED") (pin "1") (pinfunction "GND_1") (pintype "passive"))
      (node (ref "R1") (pin "2") (pintype "passive"))
      (node (ref "R17") (pin "1") (pinfunction "1_1") (pintype "passive"))
      (node (ref "R32") (pin "1") (pinfunction "1_1") (pintype "passive"))
      (node (ref "SPI2") (pin "2") (pinfunction "2_2") (pintype "passive"))
      (node (ref "SPI3") (pin "2") (pinfunction "2_2") (pintype "passive"))
      (node (ref "SW1") (pin "2") (pinfunction "2_2") (pintype "passive"))
      (node (ref "SW1") (pin "3") (pinfunction "3_3") (pintype "passive"))
      (node (ref "U1") (pin "12") (pinfunction "VSSA_12") (pintype "power_in"))
      (node (ref "U1") (pin "18") (pinfunction "VSS_18") (pintype "power_in"))
      (node (ref "U1") (pin "63") (pinfunction "VSS_63") (pintype "power_in"))
      (node (ref "U2") (pin "1") (pinfunction "GND_1") (pintype "passive"))
      (node (ref "USART2") (pin "2") (pinfunction "2_2") (pintype "passive"))
      (node (ref "USART3") (pin "2") (pinfunction "2_2") (pintype "passive"))
      (node (ref "USB1") (pin "4") (pinfunction "GND_4") (pintype "passive"))
      (node (ref "V1") (pin "1") (pinfunction "GND_1") (pintype "passive"))
      (node (ref "X1") (pin "2") (pinfunction "2_2") (pintype "passive"))
      (node (ref "X1") (pin "4") (pinfunction "4_4") (pintype "passive"))
      (node (ref "X2") (pin "2") (pinfunction "2_2") (pintype "passive"))
      (node (ref "X2") (pin "4") (pinfunction "4_4") (pintype "passive"))
    )
    (net (code "59") (name "Net-(C22-Pad1)") (class "Default")
      (node (ref "C22") (pin "1") (pinfunction "1_1") (pintype "passive"))
      (node (ref "R20") (pin "1") (pinfunction "1_1") (pintype "passive"))
      (node (ref "R24") (pin "1") (pinfunction "1_1") (pintype "passive"))
      (node (ref "R29") (pin "1") (pinfunction "1_1") (pintype "passive"))
    )
    (net (code "60") (name "Net-(C32-Pad1)") (class "Default")
      (node (ref "C32") (pin "1") (pinfunction "1_1") (pintype "passive"))
      (node (ref "R33") (pin "1") (pinfunction "1_1") (pintype "passive"))
      (node (ref "R37") (pin "1") (pinfunction "1_1") (pintype "passive"))
      (node (ref "R44") (pin "1") (pinfunction "1_1") (pintype "passive"))
    )
    (net (code "61") (name "Net-(CON1-Pad1)") (class "Default")
      (node (ref "CON1") (pin "1") (pintype "power_in"))
      (node (ref "F1") (pin "1") (pinfunction "1_1") (pintype "passive"))
    )
    (net (code "62") (name "Net-(D1-K)") (class "Default")
      (node (ref "C4") (pin "1") (pinfunction "1_1") (pintype "passive"))
      (node (ref "D1") (pin "2") (pinfunction "K_2") (pintype "passive"))
      (node (ref "L2") (pin "1") (pinfunction "1_1") (pintype "passive"))
      (node (ref "U3") (pin "6") (pinfunction "SW_6") (pintype "passive"))
    )
    (net (code "63") (name "Net-(IC1-S)") (class "Default")
      (node (ref "IC1") (pin "8") (pinfunction "S_8") (pintype "passive"))
      (node (ref "R17") (pin "2") (pinfunction "2_2") (pintype "passive"))
    )
    (net (code "64") (name "Net-(IC1-VREF)") (class "Default")
      (node (ref "IC1") (pin "5") (pinfunction "VREF_5") (pintype "passive"))
      (node (ref "R24") (pin "2") (pinfunction "2_2") (pintype "passive"))
    )
    (net (code "65") (name "Net-(IC2-S)") (class "Default")
      (node (ref "IC2") (pin "8") (pinfunction "S_8") (pintype "passive"))
      (node (ref "R32") (pin "2") (pinfunction "2_2") (pintype "passive"))
    )
    (net (code "66") (name "Net-(IC2-VREF)") (class "Default")
      (node (ref "IC2") (pin "5") (pinfunction "VREF_5") (pintype "passive"))
      (node (ref "R37") (pin "2") (pinfunction "2_2") (pintype "passive"))
    )
    (net (code "67") (name "Net-(J1-1A)") (class "Default")
      (node (ref "C18") (pin "2") (pinfunction "2_2") (pintype "passive"))
      (node (ref "J1") (pin "1") (pinfunction "1A_1") (pintype "passive"))
      (node (ref "R18") (pin "2") (pintype "passive"))
    )
    (net (code "68") (name "Net-(J1-2A)") (class "Default")
      (node (ref "C21") (pin "2") (pinfunction "2_2") (pintype "passive"))
      (node (ref "J1") (pin "3") (pinfunction "2A_3") (pintype "passive"))
      (node (ref "R21") (pin "2") (pintype "passive"))
    )
    (net (code "69") (name "Net-(J1-3A)") (class "Default")
      (node (ref "C24") (pin "2") (pinfunction "2_2") (pintype "passive"))
      (node (ref "J1") (pin "5") (pinfunction "3A_5") (pintype "passive"))
      (node (ref "R26") (pin "2") (pintype "passive"))
    )
    (net (code "70") (name "Net-(J1-4A)") (class "Default")
      (node (ref "C26") (pin "2") (pinfunction "2_2") (pintype "passive"))
      (node (ref "J1") (pin "7") (pinfunction "4A_7") (pintype "passive"))
      (node (ref "R30") (pin "2") (pintype "passive"))
    )
    (net (code "71") (name "Net-(LED1-PadA)") (class "Default")
      (node (ref "LED1") (pin "A") (pinfunction "A_A") (pintype "passive"))
      (node (ref "R2") (pin "2") (pintype "passive"))
    )
    (net (code "72") (name "Net-(LED2-K)") (class "Default")
      (node (ref "LED2") (pin "2") (pinfunction "K_2") (pintype "passive"))
      (node (ref "R7") (pin "2") (pinfunction "2_2") (pintype "passive"))
    )
    (net (code "73") (name "Net-(LED4-PadA)") (class "Default")
      (node (ref "LED4") (pin "A") (pinfunction "A_A") (pintype "passive"))
      (node (ref "R3") (pin "2") (pintype "passive"))
    )
    (net (code "74") (name "Net-(LED5-PadA)") (class "Default")
      (node (ref "LED5") (pin "A") (pinfunction "A_A") (pintype "passive"))
      (node (ref "R12") (pin "1") (pintype "passive"))
    )
    (net (code "75") (name "Net-(LED6-PadA)") (class "Default")
      (node (ref "LED6") (pin "A") (pinfunction "A_A") (pintype "passive"))
      (node (ref "R13") (pin "1") (pintype "passive"))
    )
    (net (code "76") (name "Net-(LED7-PadA)") (class "Default")
      (node (ref "LED7") (pin "A") (pinfunction "A_A") (pintype "passive"))
      (node (ref "R19") (pin "1") (pintype "passive"))
    )
    (net (code "77") (name "Net-(LED8-PadA)") (class "Default")
      (node (ref "LED8") (pin "A") (pinfunction "A_A") (pintype "passive"))
      (node (ref "R22") (pin "1") (pintype "passive"))
    )
    (net (code "78") (name "Net-(LED9-PadA)") (class "Default")
      (node (ref "LED9") (pin "A") (pinfunction "A_A") (pintype "passive"))
      (node (ref "R28") (pin "1") (pintype "passive"))
    )
    (net (code "79") (name "Net-(LED10-PadA)") (class "Default")
      (node (ref "LED10") (pin "A") (pinfunction "A_A") (pintype "passive"))
      (node (ref "R31") (pin "1") (pintype "passive"))
    )
    (net (code "80") (name "Net-(Q1-B)") (class "Default")
      (node (ref "Q1") (pin "1") (pinfunction "B_1") (pintype "passive"))
      (node (ref "R25") (pin "2") (pintype "passive"))
      (node (ref "R27") (pin "2") (pintype "passive"))
    )
    (net (code "81") (name "Net-(Q1-C)") (class "Default")
      (node (ref "C20") (pin "1") (pinfunction "1_1") (pintype "passive"))
      (node (ref "JP1") (pin "2") (pinfunction "2_2") (pintype "passive"))
      (node (ref "Q1") (pin "3") (pinfunction "C_3") (pintype "passive"))
      (node (ref "R23") (pin "1") (pintype "passive"))
    )
    (net (code "82") (name "Net-(Q2-B)") (class "Default")
      (node (ref "Q2") (pin "1") (pinfunction "B_1") (pintype "passive"))
      (node (ref "R38") (pin "2") (pintype "passive"))
      (node (ref "R41") (pin "2") (pintype "passive"))
    )
    (net (code "83") (name "Net-(Q2-C)") (class "Default")
      (node (ref "C29") (pin "1") (pinfunction "1_1") (pintype "passive"))
      (node (ref "JP2") (pin "2") (pinfunction "2_2") (pintype "passive"))
      (node (ref "Q2") (pin "3") (pinfunction "C_3") (pintype "passive"))
      (node (ref "R34") (pin "1") (pintype "passive"))
    )
    (net (code "84") (name "Net-(Q3-B)") (class "Default")
      (node (ref "Q3") (pin "1") (pinfunction "B_1") (pintype "passive"))
      (node (ref "R39") (pin "2") (pintype "passive"))
      (node (ref "R42") (pin "2") (pintype "passive"))
    )
    (net (code "85") (name "Net-(Q3-C)") (class "Default")
      (node (ref "C30") (pin "1") (pinfunction "1_1") (pintype "passive"))
      (node (ref "JP3") (pin "2") (pinfunction "2_2") (pintype "passive"))
      (node (ref "Q3") (pin "3") (pinfunction "C_3") (pintype "passive"))
      (node (ref "R35") (pin "1") (pintype "passive"))
    )
    (net (code "86") (name "Net-(Q4-B)") (class "Default")
      (node (ref "Q4") (pin "1") (pinfunction "B_1") (pintype "passive"))
      (node (ref "R40") (pin "2") (pintype "passive"))
      (node (ref "R43") (pin "2") (pintype "passive"))
    )
    (net (code "87") (name "Net-(Q4-C)") (class "Default")
      (node (ref "C31") (pin "1") (pinfunction "1_1") (pintype "passive"))
      (node (ref "JP4") (pin "2") (pinfunction "2_2") (pintype "passive"))
      (node (ref "Q4") (pin "3") (pinfunction "C_3") (pintype "passive"))
      (node (ref "R36") (pin "1") (pintype "passive"))
    )
    (net (code "88") (name "Net-(U1-BOOT0)") (class "Default")
      (node (ref "R1") (pin "1") (pintype "passive"))
      (node (ref "U1") (pin "60") (pinfunction "BOOT0_60") (pintype "input"))
    )
    (net (code "89") (name "Net-(U1-VCAP_1)") (class "Default")
      (node (ref "C16") (pin "1") (pinfunction "1_1") (pintype "passive"))
      (node (ref "U1") (pin "31") (pinfunction "VCAP_1_31") (pintype "power_in"))
    )
    (net (code "90") (name "Net-(U1-VCAP_2)") (class "Default")
      (node (ref "C17") (pin "1") (pinfunction "1_1") (pintype "passive"))
      (node (ref "U1") (pin "47") (pinfunction "VCAP_2_47") (pintype "power_in"))
    )
    (net (code "91") (name "Net-(U1-VDDA)") (class "Default")
      (node (ref "C2") (pin "1") (pinfunction "1_1") (pintype "passive"))
      (node (ref "C3") (pin "1") (pinfunction "1_1") (pintype "passive"))
      (node (ref "L1") (pin "2") (pinfunction "2_2") (pintype "passive"))
      (node (ref "U1") (pin "13") (pinfunction "VDDA_13") (pintype "power_in"))
    )
    (net (code "92") (name "Net-(U2-RxD)") (class "Default")
      (node (ref "R5") (pin "2") (pintype "passive"))
      (node (ref "U2") (pin "3") (pinfunction "RxD_3") (pintype "passive"))
    )
    (net (code "93") (name "Net-(U2-TxD)") (class "Default")
      (node (ref "R4") (pin "2") (pintype "passive"))
      (node (ref "U2") (pin "2") (pinfunction "TxD_2") (pintype "passive"))
    )
    (net (code "94") (name "Net-(U2-XI)") (class "Default")
      (node (ref "C10") (pin "2") (pinfunction "2_2") (pintype "passive"))
      (node (ref "U2") (pin "7") (pinfunction "XI_7") (pintype "passive"))
      (node (ref "X1") (pin "1") (pinfunction "1_1") (pintype "passive"))
    )
    (net (code "95") (name "Net-(U2-XO)") (class "Default")
      (node (ref "C11") (pin "2") (pinfunction "2_2") (pintype "passive"))
      (node (ref "U2") (pin "8") (pinfunction "XO_8") (pintype "passive"))
      (node (ref "X1") (pin "3") (pinfunction "3_3") (pintype "passive"))
    )
    (net (code "96") (name "Net-(U3-CB)") (class "Default")
      (node (ref "C4") (pin "2") (pinfunction "2_2") (pintype "passive"))
      (node (ref "U3") (pin "1") (pinfunction "CB_1") (pintype "passive"))
    )
    (net (code "97") (name "unconnected-(J2-JTDI-Pad6)") (class "Default")
      (node (ref "J2") (pin "6") (pinfunction "JTDI_6") (pintype "passive+no_connect"))
    )
    (net (code "98") (name "unconnected-(J2-JTDO-Pad8)") (class "Default")
      (node (ref "J2") (pin "8") (pinfunction "JTDO_8") (pintype "passive+no_connect"))
    )
    (net (code "99") (name "unconnected-(J2-JTRst-Pad5)") (class "Default")
      (node (ref "J2") (pin "5") (pinfunction "JTRst_5") (pintype "passive+no_connect"))
    )
    (net (code "100") (name "unconnected-(J2-VSS-Pad7)") (class "Default")
      (node (ref "J2") (pin "7") (pinfunction "VSS_7") (pintype "passive+no_connect"))
    )
    (net (code "101") (name "unconnected-(SP1-Pad1)") (class "Default")
      (node (ref "SP1") (pin "1") (pinfunction "1_1") (pintype "passive"))
    )
    (net (code "102") (name "unconnected-(SP2-Pad1)") (class "Default")
      (node (ref "SP2") (pin "1") (pinfunction "1_1") (pintype "passive"))
    )
    (net (code "103") (name "unconnected-(SP3-Pad1)") (class "Default")
      (node (ref "SP3") (pin "1") (pinfunction "1_1") (pintype "passive"))
    )
    (net (code "104") (name "unconnected-(SP4-Pad1)") (class "Default")
      (node (ref "SP4") (pin "1") (pinfunction "1_1") (pintype "passive"))
    )
    (net (code "105") (name "unconnected-(U1-PA0_WKUP-Pad14)") (class "Default")
      (node (ref "U1") (pin "14") (pinfunction "PA0_WKUP_14") (pintype "bidirectional"))
    )
    (net (code "106") (name "unconnected-(U1-PA1-Pad15)") (class "Default")
      (node (ref "U1") (pin "15") (pinfunction "PA1_15") (pintype "bidirectional"))
    )
    (net (code "107") (name "unconnected-(U1-PB0-Pad26)") (class "Default")
      (node (ref "U1") (pin "26") (pinfunction "PB0_26") (pintype "bidirectional"))
    )
    (net (code "108") (name "unconnected-(U1-PB1-Pad27)") (class "Default")
      (node (ref "U1") (pin "27") (pinfunction "PB1_27") (pintype "bidirectional"))
    )
    (net (code "109") (name "unconnected-(U1-PB8-Pad61)") (class "Default")
      (node (ref "U1") (pin "61") (pinfunction "PB8_61") (pintype "bidirectional"))
    )
    (net (code "110") (name "unconnected-(U1-PB11-Pad30)") (class "Default")
      (node (ref "U1") (pin "30") (pinfunction "PB11_30") (pintype "bidirectional"))
    )
    (net (code "111") (name "unconnected-(U1-PC0-Pad8)") (class "Default")
      (node (ref "U1") (pin "8") (pinfunction "PC0_8") (pintype "bidirectional"))
    )
    (net (code "112") (name "unconnected-(U1-PC1-Pad9)") (class "Default")
      (node (ref "U1") (pin "9") (pinfunction "PC1_9") (pintype "bidirectional"))
    )
    (net (code "113") (name "unconnected-(U1-PC5-Pad25)") (class "Default")
      (node (ref "U1") (pin "25") (pinfunction "PC5_25") (pintype "bidirectional"))
    )
    (net (code "114") (name "unconnected-(U1-PC6-Pad37)") (class "Default")
      (node (ref "U1") (pin "37") (pinfunction "PC6_37") (pintype "bidirectional"))
    )
    (net (code "115") (name "unconnected-(U1-PC7-Pad38)") (class "Default")
      (node (ref "U1") (pin "38") (pinfunction "PC7_38") (pintype "bidirectional"))
    )
    (net (code "116") (name "unconnected-(U1-PC12-Pad53)") (class "Default")
      (node (ref "U1") (pin "53") (pinfunction "PC12_53") (pintype "bidirectional"))
    )
    (net (code "117") (name "unconnected-(U1-PC13-Pad2)") (class "Default")
      (node (ref "U1") (pin "2") (pinfunction "PC13_2") (pintype "bidirectional"))
    )
    (net (code "118") (name "unconnected-(U1-PC14-Pad3)") (class "Default")
      (node (ref "U1") (pin "3") (pinfunction "PC14_3") (pintype "bidirectional"))
    )
    (net (code "119") (name "unconnected-(U1-PC15-Pad4)") (class "Default")
      (node (ref "U1") (pin "4") (pinfunction "PC15_4") (pintype "bidirectional"))
    )
    (net (code "120") (name "unconnected-(U1-PD2-Pad54)") (class "Default")
      (node (ref "U1") (pin "54") (pinfunction "PD2_54") (pintype "bidirectional"))
    )
    (net (code "121") (name "unconnected-(U2-CTS#-Pad9)") (class "Default")
      (node (ref "U2") (pin "9") (pinfunction "CTS#_9") (pintype "passive+no_connect"))
    )
    (net (code "122") (name "unconnected-(U2-DCD#-Pad12)") (class "Default")
      (node (ref "U2") (pin "12") (pinfunction "DCD#_12") (pintype "passive+no_connect"))
    )
    (net (code "123") (name "unconnected-(U2-DSR#-Pad10)") (class "Default")
      (node (ref "U2") (pin "10") (pinfunction "DSR#_10") (pintype "passive+no_connect"))
    )
    (net (code "124") (name "unconnected-(U2-DTR#-Pad13)") (class "Default")
      (node (ref "U2") (pin "13") (pinfunction "DTR#_13") (pintype "passive+no_connect"))
    )
    (net (code "125") (name "unconnected-(U2-RI#-Pad11)") (class "Default")
      (node (ref "U2") (pin "11") (pinfunction "RI#_11") (pintype "passive+no_connect"))
    )
    (net (code "126") (name "unconnected-(U2-RS232-Pad15)") (class "Default")
      (node (ref "U2") (pin "15") (pinfunction "RS232_15") (pintype "passive+no_connect"))
    )
    (net (code "127") (name "unconnected-(U2-RTS#-Pad14)") (class "Default")
      (node (ref "U2") (pin "14") (pinfunction "RTS#_14") (pintype "passive+no_connect"))
    )
    (net (code "128") (name "unconnected-(U3-~{SHDN}-Pad4)") (class "Default")
      (node (ref "U3") (pin "4") (pinfunction "~{SHDN}_4") (pintype "input+no_connect"))
    )
  )
)
